# RCSfullschematic3.net
KiCad netlist of a schematic drawn in EAGLE
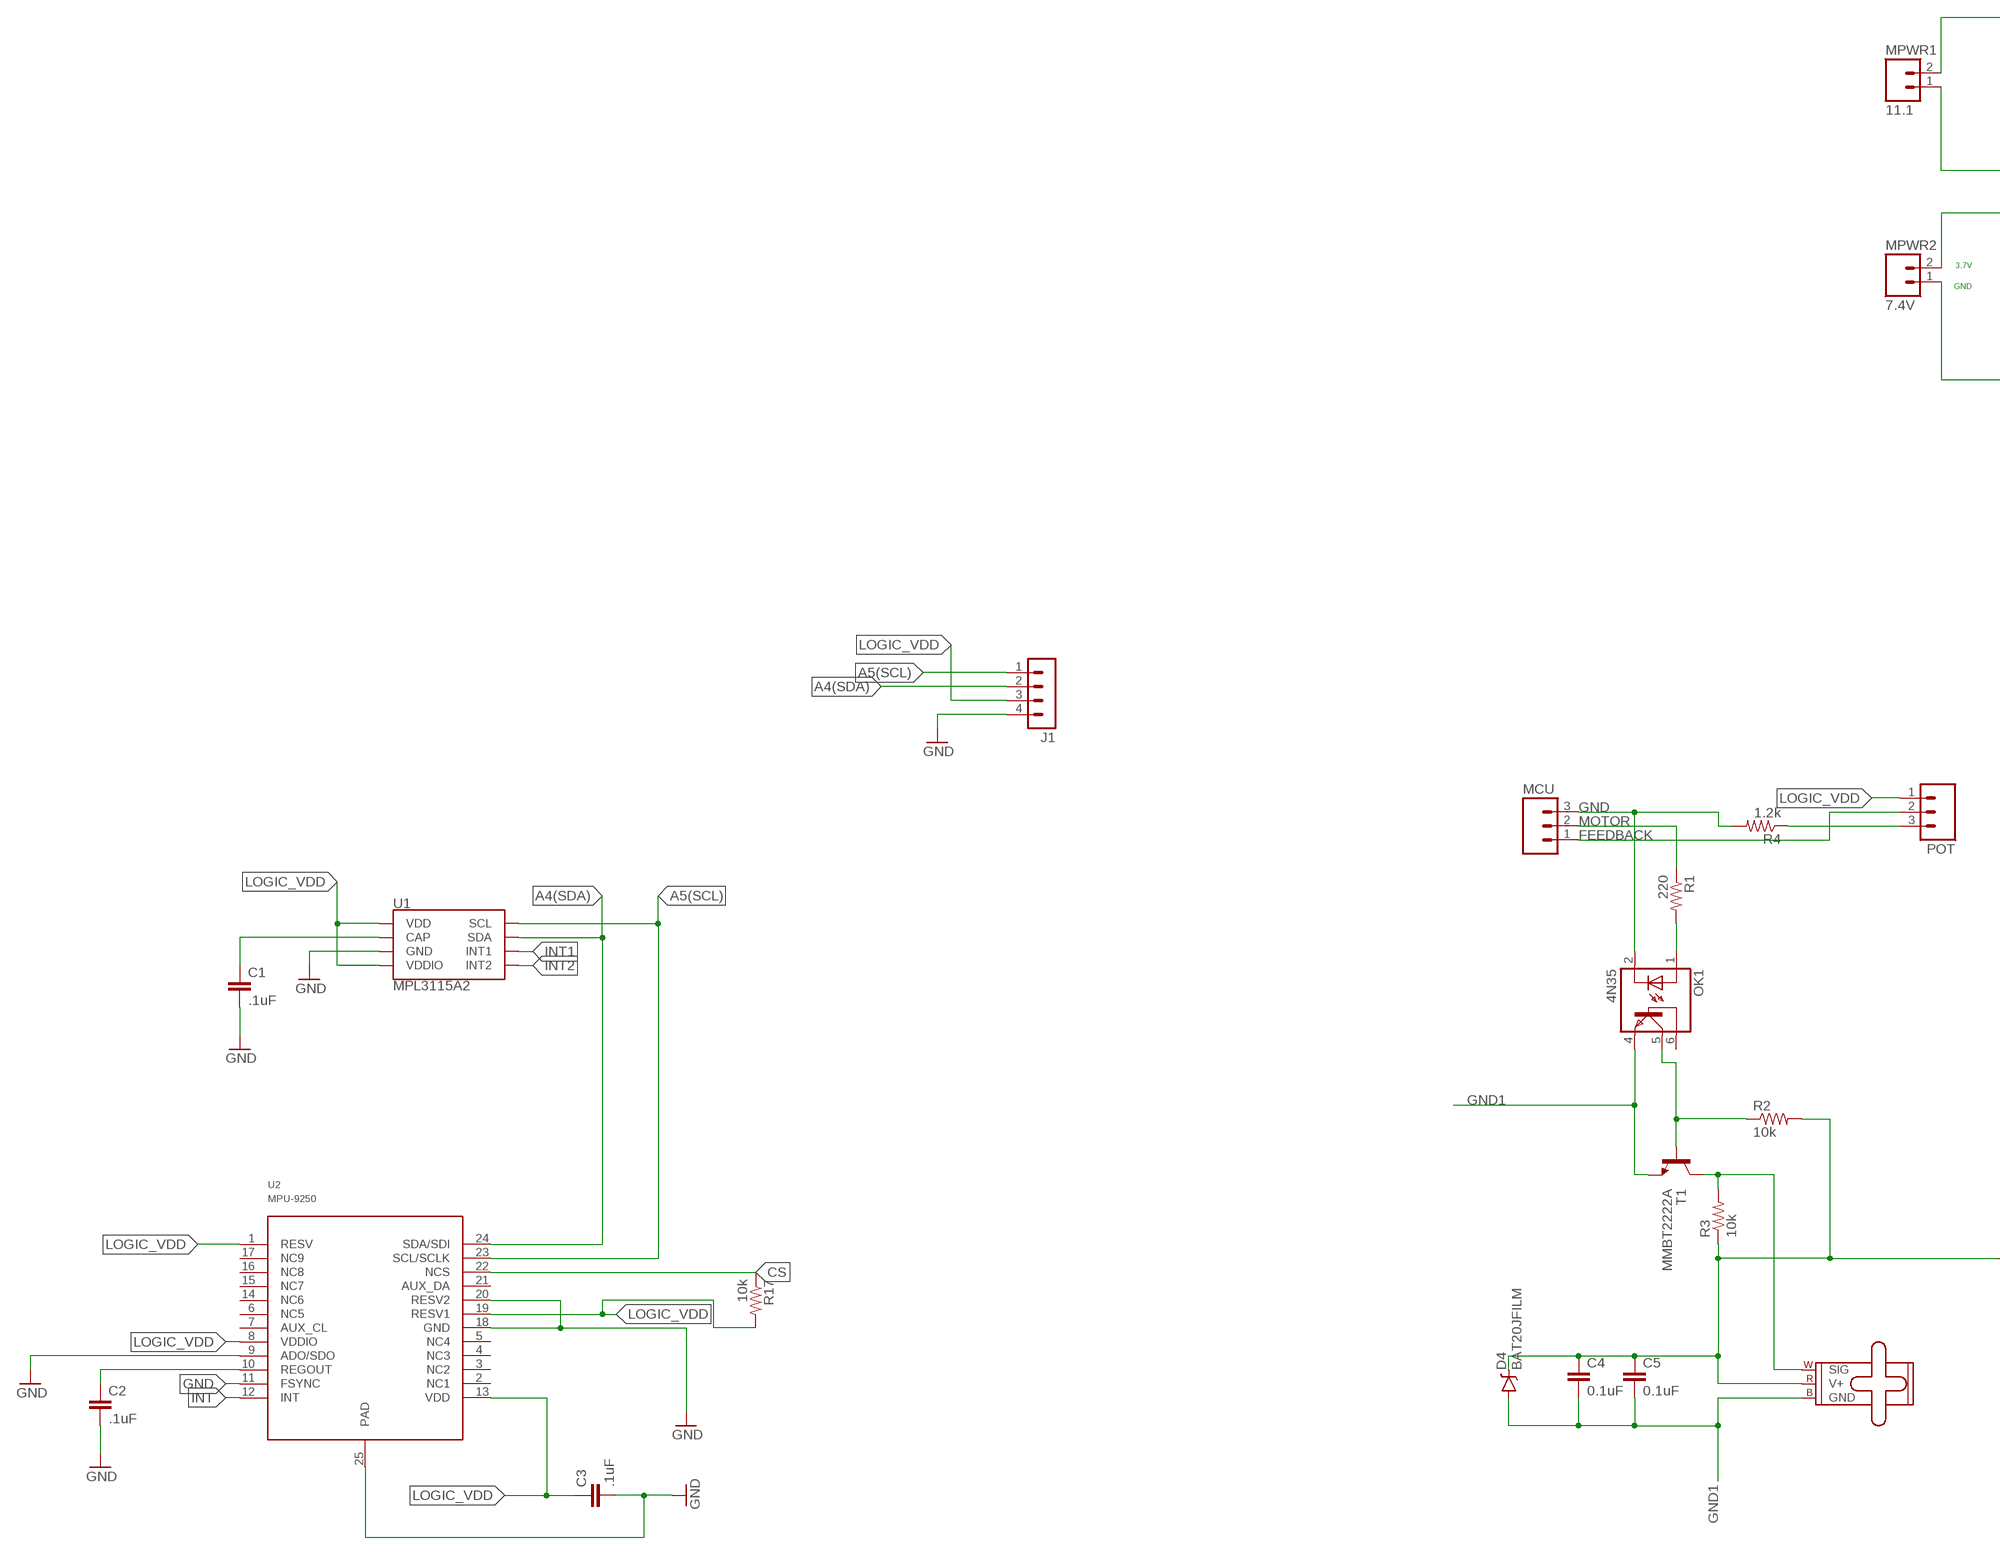
[diagram p0: schematic, sheet 1, part 1 of 2]
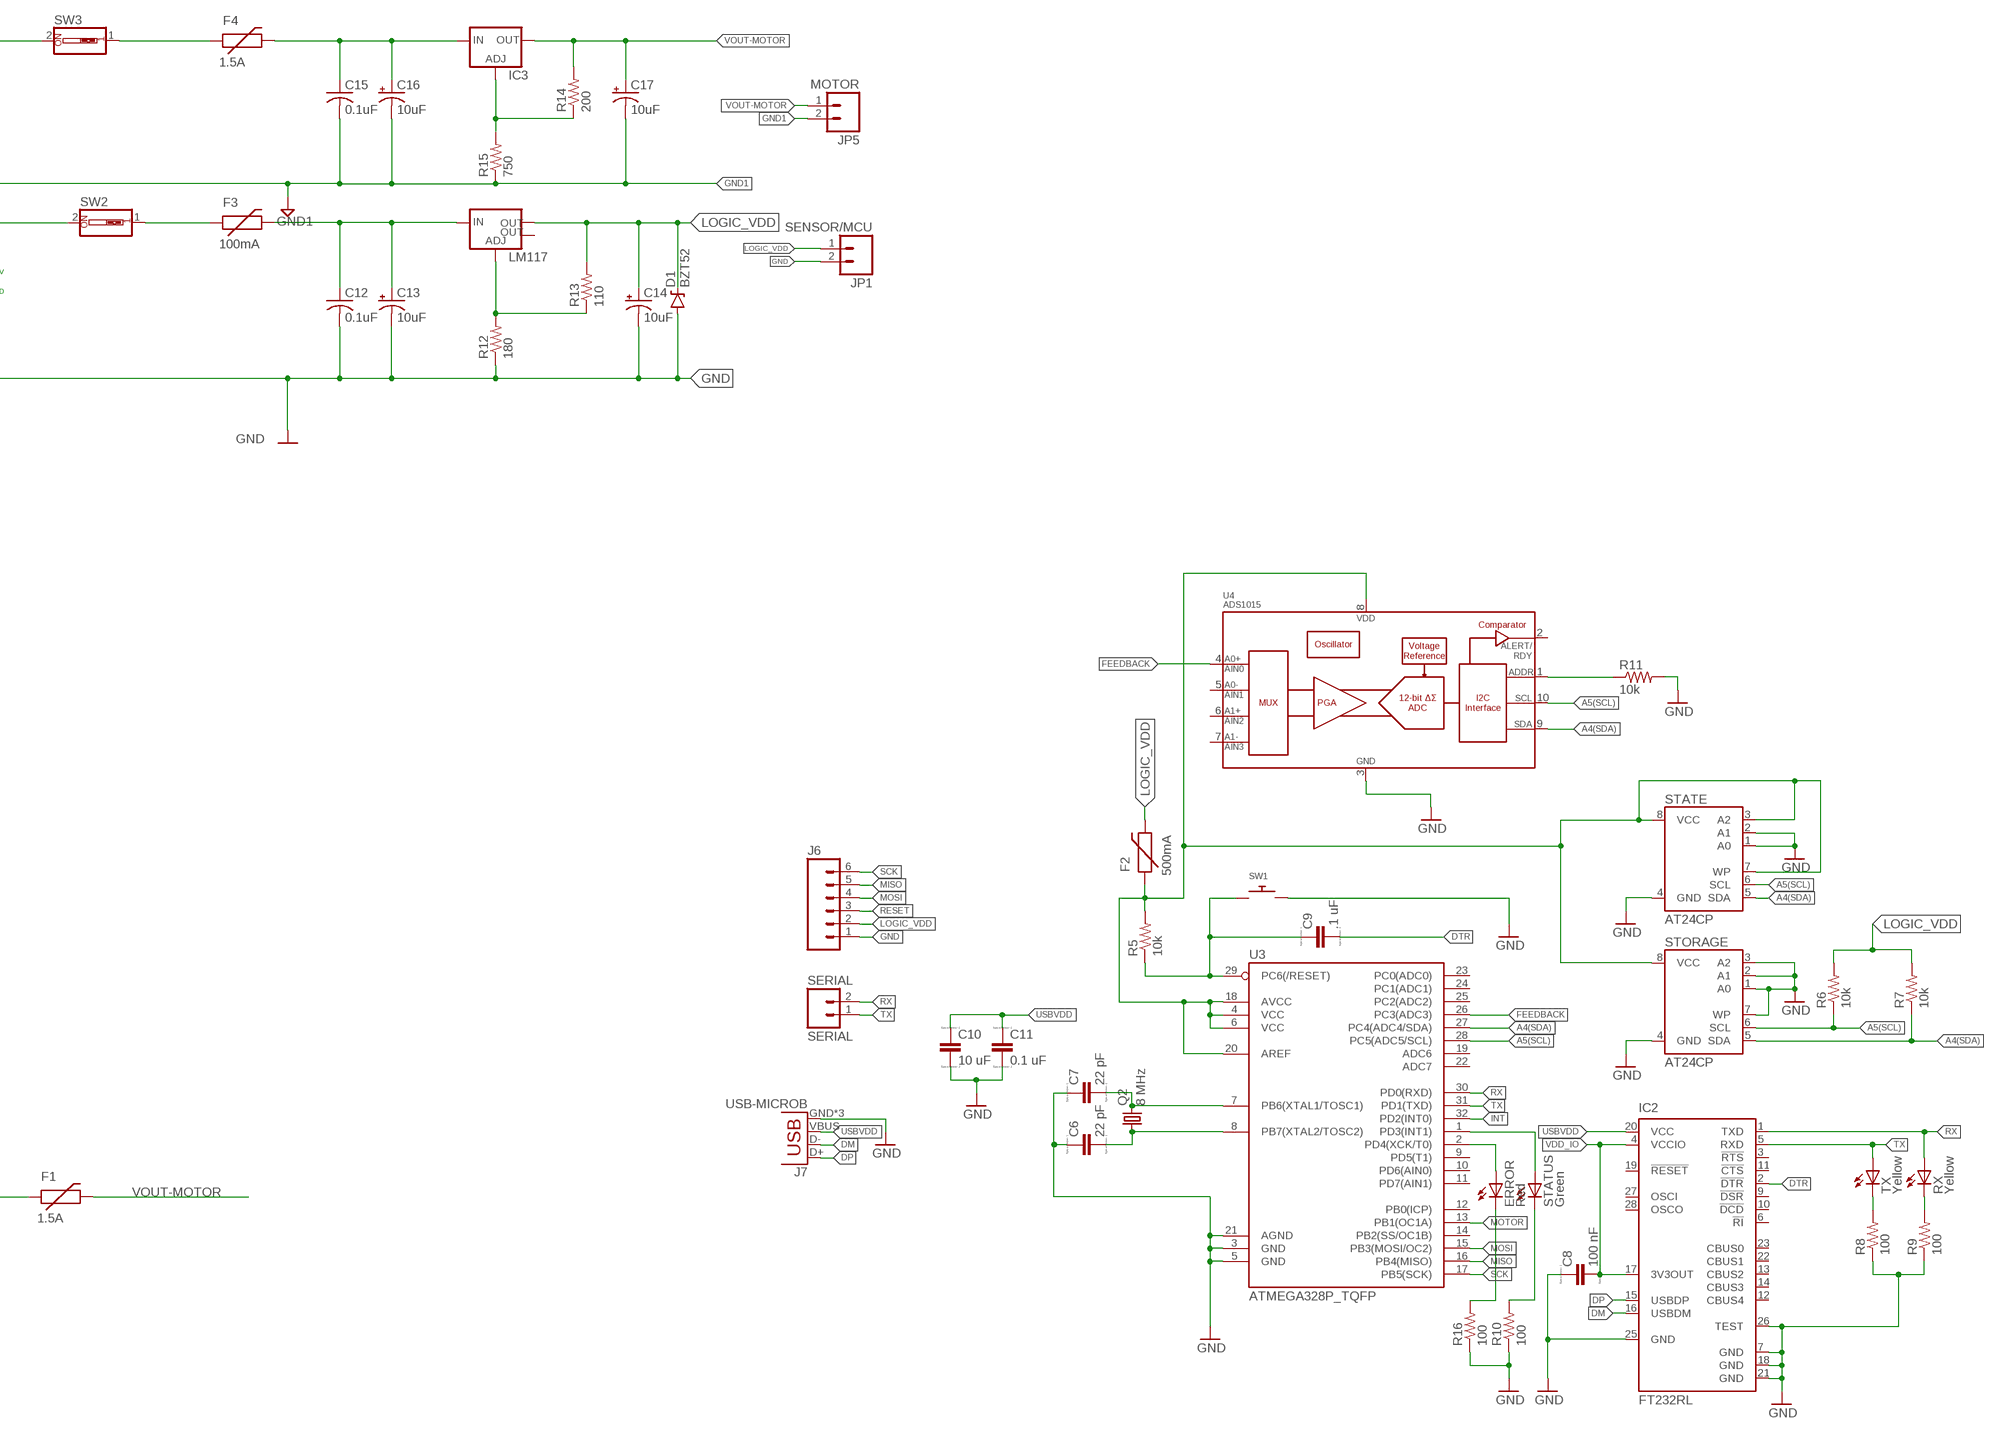
[diagram p1: schematic, sheet 1, part 2 of 2]

(export (version "E")
  (design (tool "Eeschema 10.0.6"))
  (components
    (comp (ref "C1")
      (value ".1uF")
      (footprint "eagle-import:1206")
      (libsource (lib "eagle-import") (part "10UF-1206-6.3V-20%"))
    )
    (comp (ref "C2")
      (value ".1uF")
      (footprint "eagle-import:1206")
      (libsource (lib "eagle-import") (part "10UF-1206-6.3V-20%"))
    )
    (comp (ref "C3")
      (value ".1uF")
      (footprint "eagle-import:1206")
      (libsource (lib "eagle-import") (part "10UF-1206-6.3V-20%"))
    )
    (comp (ref "C4")
      (value "0.1uF")
      (footprint "eagle-import:1206")
      (libsource (lib "eagle-import") (part "CAP1206"))
    )
    (comp (ref "C5")
      (value "0.1uF")
      (footprint "eagle-import:1206")
      (libsource (lib "eagle-import") (part "CAP1206"))
    )
    (comp (ref "C6")
      (value "22 pF")
      (footprint "eagle-import:C1206")
      (libsource (lib "eagle-import") (part "CC1206"))
    )
    (comp (ref "C7")
      (value "22 pF")
      (footprint "eagle-import:C1206")
      (libsource (lib "eagle-import") (part "CC1206"))
    )
    (comp (ref "C8")
      (value "100 nF")
      (footprint "eagle-import:C1206")
      (libsource (lib "eagle-import") (part "CC1206"))
    )
    (comp (ref "C9")
      (value ".1 uF")
      (footprint "eagle-import:C1206")
      (libsource (lib "eagle-import") (part "CC1206"))
    )
    (comp (ref "C10")
      (value "10 uF")
      (footprint "eagle-import:C1206")
      (libsource (lib "eagle-import") (part "CC1206"))
    )
    (comp (ref "C11")
      (value "0.1 uF")
      (footprint "eagle-import:C1206")
      (libsource (lib "eagle-import") (part "CC1206"))
    )
    (comp (ref "C12")
      (value "0.1uF")
      (footprint "eagle-import:C1206")
      (libsource (lib "eagle-import") (part "C-USC1206"))
    )
    (comp (ref "C13")
      (value "10uF")
      (footprint "eagle-import:EIA3216")
      (libsource (lib "eagle-import") (part "10UF-POLAR-EIA3216-16V-10%(TANT)"))
    )
    (comp (ref "C14")
      (value "10uF")
      (footprint "eagle-import:EIA3216")
      (libsource (lib "eagle-import") (part "10UF-POLAR-EIA3216-16V-10%(TANT)"))
    )
    (comp (ref "C15")
      (value "0.1uF")
      (footprint "eagle-import:C1206")
      (libsource (lib "eagle-import") (part "C-USC1206"))
    )
    (comp (ref "C16")
      (value "10uF")
      (footprint "eagle-import:EIA3216")
      (libsource (lib "eagle-import") (part "10UF-POLAR-EIA3216-16V-10%(TANT)"))
    )
    (comp (ref "C17")
      (value "10uF")
      (footprint "eagle-import:EIA3216")
      (libsource (lib "eagle-import") (part "10UF-POLAR-EIA3216-16V-10%(TANT)"))
    )
    (comp (ref "D1")
      (value "BZT52")
      (footprint "eagle-import:DIODE-BZT52")
      (libsource (lib "eagle-import") (part "DIODE-ZENER"))
    )
    (comp (ref "D4")
      (value "BAT20JFILM")
      (footprint "eagle-import:SOD-323")
      (libsource (lib "eagle-import") (part "BAT20JFILM"))
    )
    (comp (ref "ERROR")
      (value "Red")
      (footprint "eagle-import:CHIPLED_1206")
      (libsource (lib "eagle-import") (part "LEDCHIPLED_1206"))
    )
    (comp (ref "F1")
      (value "1.5A")
      (footprint "eagle-import:PTC-1206")
      (libsource (lib "eagle-import") (part "PTCSMD"))
    )
    (comp (ref "F2")
      (value "500mA")
      (footprint "eagle-import:PTC-1206")
      (libsource (lib "eagle-import") (part "PTCSMD"))
    )
    (comp (ref "F3")
      (value "100mA")
      (footprint "eagle-import:PTC-1206")
      (libsource (lib "eagle-import") (part "PTCSMD"))
    )
    (comp (ref "F4")
      (value "1.5A")
      (footprint "eagle-import:PTC-1206")
      (libsource (lib "eagle-import") (part "PTCSMD"))
    )
    (comp (ref "IC2")
      (value "FT232RL")
      (footprint "eagle-import:SSOP28")
      (libsource (lib "eagle-import") (part "FT232RL"))
    )
    (comp (ref "IC3")
      (value "LM317TS")
      (footprint "eagle-import:317TS")
      (libsource (lib "eagle-import") (part "LM317TS"))
    )
    (comp (ref "J1")
      (value "MA04-1")
      (footprint "eagle-import:MA04-1")
      (libsource (lib "eagle-import") (part "MA04-1"))
    )
    (comp (ref "J6")
      (value "M06LOCK")
      (footprint "eagle-import:1X06_LOCK")
      (libsource (lib "eagle-import") (part "M06LOCK"))
    )
    (comp (ref "J7")
      (value "USB-MICROB")
      (footprint "eagle-import:USB-MICROB")
      (libsource (lib "eagle-import") (part "USB-MICROB"))
    )
    (comp (ref "JP1")
      (value "SENSOR/MCU")
      (footprint "eagle-import:1X02")
      (libsource (lib "eagle-import") (part "M02PTH"))
    )
    (comp (ref "JP5")
      (value "MOTOR")
      (footprint "eagle-import:1X02")
      (libsource (lib "eagle-import") (part "M02PTH"))
    )
    (comp (ref "LM117")
      (value "V_REG_LM1117SOT223")
      (footprint "eagle-import:SOT223")
      (libsource (lib "eagle-import") (part "V_REG_LM1117SOT223"))
    )
    (comp (ref "MCU")
      (value "M03PTH")
      (footprint "eagle-import:1X03")
      (libsource (lib "eagle-import") (part "M03PTH"))
    )
    (comp (ref "MPWR1")
      (value "11.1")
      (footprint "eagle-import:1X02")
      (libsource (lib "eagle-import") (part "M02PTH"))
    )
    (comp (ref "MPWR2")
      (value "7.4V")
      (footprint "eagle-import:1X02")
      (libsource (lib "eagle-import") (part "M02PTH"))
    )
    (comp (ref "OK1")
      (value "4N35")
      (footprint "eagle-import:DIL06")
      (fields (field (name "MF") "FAIRCHILD SEMICONDUCTOR"))
      (libsource (lib "eagle-import") (part "4N35"))
    )
    (comp (ref "POT")
      (value "M03PTH")
      (footprint "eagle-import:1X03")
      (libsource (lib "eagle-import") (part "M03PTH"))
    )
    (comp (ref "Q2")
      (value "8 MHz")
      (footprint "eagle-import:HC49_S")
      (libsource (lib "eagle-import") (part "CRYSTALHC49S"))
    )
    (comp (ref "R1")
      (value "220")
      (footprint "eagle-import:1206")
      (libsource (lib "eagle-import") (part "RESISTOR1206"))
    )
    (comp (ref "R2")
      (value "10k")
      (footprint "eagle-import:1206")
      (libsource (lib "eagle-import") (part "RESISTOR1206"))
    )
    (comp (ref "R3")
      (value "10k")
      (footprint "eagle-import:1206")
      (libsource (lib "eagle-import") (part "RESISTOR1206"))
    )
    (comp (ref "R4")
      (value "1.2k")
      (footprint "eagle-import:1206")
      (libsource (lib "eagle-import") (part "RESISTOR1206"))
    )
    (comp (ref "R5")
      (value "10k")
      (footprint "eagle-import:R1206")
      (libsource (lib "eagle-import") (part "R-US_R1206"))
    )
    (comp (ref "R6")
      (value "10k")
      (footprint "eagle-import:R1206")
      (libsource (lib "eagle-import") (part "R-US_R1206"))
    )
    (comp (ref "R7")
      (value "10k")
      (footprint "eagle-import:R1206")
      (libsource (lib "eagle-import") (part "R-US_R1206"))
    )
    (comp (ref "R8")
      (value "100")
      (footprint "eagle-import:R1206")
      (libsource (lib "eagle-import") (part "R-US_R1206"))
    )
    (comp (ref "R9")
      (value "100")
      (footprint "eagle-import:R1206")
      (libsource (lib "eagle-import") (part "R-US_R1206"))
    )
    (comp (ref "R10")
      (value "100")
      (footprint "eagle-import:R1206")
      (libsource (lib "eagle-import") (part "R-US_R1206"))
    )
    (comp (ref "R11")
      (value "10k")
      (footprint "eagle-import:R1206")
      (libsource (lib "eagle-import") (part "R-US_R1206"))
    )
    (comp (ref "R12")
      (value "180")
      (footprint "eagle-import:M1206")
      (libsource (lib "eagle-import") (part "rcl_R-US_M1206"))
    )
    (comp (ref "R13")
      (value "110")
      (footprint "eagle-import:M1206")
      (libsource (lib "eagle-import") (part "rcl_R-US_M1206"))
    )
    (comp (ref "R14")
      (value "200")
      (footprint "eagle-import:M1206")
      (libsource (lib "eagle-import") (part "rcl_R-US_M1206"))
    )
    (comp (ref "R15")
      (value "750")
      (footprint "eagle-import:M1206")
      (libsource (lib "eagle-import") (part "rcl_R-US_M1206"))
    )
    (comp (ref "R16")
      (value "100")
      (footprint "eagle-import:R1206")
      (libsource (lib "eagle-import") (part "R-US_R1206"))
    )
    (comp (ref "R17")
      (value "10k")
      (footprint "eagle-import:1206")
      (libsource (lib "eagle-import") (part "RESISTOR1206"))
    )
    (comp (ref "RX")
      (value "Yellow")
      (footprint "eagle-import:CHIPLED_1206")
      (libsource (lib "eagle-import") (part "LEDCHIPLED_1206"))
    )
    (comp (ref "SERIAL")
      (value "SERIAL")
      (footprint "eagle-import:1X02")
      (libsource (lib "eagle-import") (part "M02PTH"))
    )
    (comp (ref "SERVO")
      (value "SMALL_SERVO")
      (footprint "eagle-import:1X03")
      (libsource (lib "eagle-import") (part "SMALL_SERVO"))
    )
    (comp (ref "STATE")
      (value "AT24CP")
      (footprint "eagle-import:DIL08")
      (fields (field (name "MPN") "AT24C1024BW-SH-B"))
      (libsource (lib "eagle-import") (part "AT24CP"))
    )
    (comp (ref "STATUS")
      (value "Green")
      (footprint "eagle-import:CHIPLED_1206")
      (libsource (lib "eagle-import") (part "LEDCHIPLED_1206"))
    )
    (comp (ref "STORAGE")
      (value "AT24CP")
      (footprint "eagle-import:DIL08")
      (fields (field (name "MPN") "AT24C1024BW-SH-B"))
      (libsource (lib "eagle-import") (part "AT24CP"))
    )
    (comp (ref "SW1")
      (value "SWITCH_PUSHBUTTONSOFTTOUCHSMD_SJ")
      (footprint "eagle-import:PUSHBUTTON_SMD_SJ")
      (libsource (lib "eagle-import") (part "SWITCH_PUSHBUTTONSOFTTOUCHSMD_SJ"))
    )
    (comp (ref "SW2")
      (value "SW_DIP-1")
      (footprint "eagle-import:EDG-01")
      (libsource (lib "eagle-import") (part "SW_DIP-1"))
    )
    (comp (ref "SW3")
      (value "SW_DIP-1")
      (footprint "eagle-import:EDG-01")
      (libsource (lib "eagle-import") (part "SW_DIP-1"))
    )
    (comp (ref "T1")
      (value "MMBT2222A")
      (footprint "eagle-import:SOT23-3")
      (libsource (lib "eagle-import") (part "TRANSISTOR_NPNMMBT2222A"))
    )
    (comp (ref "TX")
      (value "Yellow")
      (footprint "eagle-import:CHIPLED_1206")
      (libsource (lib "eagle-import") (part "LEDCHIPLED_1206"))
    )
    (comp (ref "U1")
      (value "MPL3115A2")
      (footprint "eagle-import:LGA-8")
      (libsource (lib "eagle-import") (part "MPL3115A2"))
    )
    (comp (ref "U2")
      (value "MPU-9250")
      (footprint "eagle-import:LEAD-QFN24")
      (libsource (lib "eagle-import") (part "MPU-9250"))
    )
    (comp (ref "U3")
      (value "ATMEGA328P_TQFP")
      (footprint "eagle-import:TQFP32-08")
      (libsource (lib "eagle-import") (part "ATMEGA328P_TQFP"))
    )
    (comp (ref "U4")
      (value "ADS1015")
      (footprint "eagle-import:MSOP10")
      (libsource (lib "eagle-import") (part "ADS1015"))
    )
  )
  (nets
    (net (code "1") (name "A4(SDA)") (class "Default")
      (node (ref "J1") (pin "2") (pinfunction "2_2") (pintype "passive"))
      (node (ref "R7") (pin "1") (pinfunction "1_1") (pintype "passive"))
      (node (ref "STATE") (pin "5") (pinfunction "SDA_5") (pintype "bidirectional"))
      (node (ref "STORAGE") (pin "5") (pinfunction "SDA_5") (pintype "bidirectional"))
      (node (ref "U1") (pin "7") (pinfunction "SDA_7") (pintype "bidirectional"))
      (node (ref "U2") (pin "24") (pinfunction "SDA/SDI_24") (pintype "bidirectional"))
      (node (ref "U3") (pin "27") (pinfunction "PC4(ADC4/SDA)_27") (pintype "bidirectional"))
      (node (ref "U4") (pin "9") (pinfunction "SDA_9") (pintype "bidirectional"))
    )
    (net (code "2") (name "A5(SCL)") (class "Default")
      (node (ref "J1") (pin "1") (pinfunction "1_1") (pintype "passive"))
      (node (ref "R6") (pin "1") (pinfunction "1_1") (pintype "passive"))
      (node (ref "STATE") (pin "6") (pinfunction "SCL_6") (pintype "bidirectional"))
      (node (ref "STORAGE") (pin "6") (pinfunction "SCL_6") (pintype "bidirectional"))
      (node (ref "U1") (pin "8") (pinfunction "SCL_8") (pintype "bidirectional"))
      (node (ref "U2") (pin "23") (pinfunction "SCL/SCLK_23") (pintype "bidirectional"))
      (node (ref "U3") (pin "28") (pinfunction "PC5(ADC5/SCL)_28") (pintype "bidirectional"))
      (node (ref "U4") (pin "10") (pinfunction "SCL_10") (pintype "bidirectional"))
    )
    (net (code "3") (name "CS") (class "Default")
      (node (ref "R17") (pin "1") (pinfunction "1_1") (pintype "passive"))
      (node (ref "U2") (pin "22") (pinfunction "NCS_22") (pintype "bidirectional"))
    )
    (net (code "4") (name "DM") (class "Default")
      (node (ref "IC2") (pin "16") (pinfunction "USBDM_16") (pintype "bidirectional"))
      (node (ref "J7") (pin "D-") (pinfunction "D-_D-") (pintype "bidirectional"))
    )
    (net (code "5") (name "DP") (class "Default")
      (node (ref "IC2") (pin "15") (pinfunction "USBDP_15") (pintype "bidirectional"))
      (node (ref "J7") (pin "D+") (pinfunction "D+_D+") (pintype "bidirectional"))
    )
    (net (code "6") (name "DTR") (class "Default")
      (node (ref "C9") (pin "2") (pinfunction "2_2") (pintype "passive"))
      (node (ref "IC2") (pin "2") (pinfunction "~{DTR}_2") (pintype "output"))
    )
    (net (code "7") (name "FEEDBACK") (class "Default")
      (node (ref "MCU") (pin "1") (pinfunction "1_1") (pintype "passive"))
      (node (ref "POT") (pin "2") (pinfunction "2_2") (pintype "passive"))
      (node (ref "U3") (pin "26") (pinfunction "PC3(ADC3)_26") (pintype "bidirectional"))
      (node (ref "U4") (pin "4") (pinfunction "AIN0_4") (pintype "bidirectional"))
    )
    (net (code "8") (name "GND") (class "Default")
      (node (ref "C1") (pin "2") (pinfunction "2_2") (pintype "passive"))
      (node (ref "C10") (pin "2") (pinfunction "2_2") (pintype "passive"))
      (node (ref "C11") (pin "2") (pinfunction "2_2") (pintype "passive"))
      (node (ref "C12") (pin "2") (pinfunction "2_2") (pintype "passive"))
      (node (ref "C13") (pin "-") (pinfunction "-_-") (pintype "passive"))
      (node (ref "C14") (pin "-") (pinfunction "-_-") (pintype "passive"))
      (node (ref "C2") (pin "2") (pinfunction "2_2") (pintype "passive"))
      (node (ref "C3") (pin "2") (pinfunction "2_2") (pintype "passive"))
      (node (ref "C6") (pin "1") (pinfunction "1_1") (pintype "passive"))
      (node (ref "C7") (pin "1") (pinfunction "1_1") (pintype "passive"))
      (node (ref "C8") (pin "1") (pinfunction "1_1") (pintype "passive"))
      (node (ref "D1") (pin "A") (pinfunction "A_A") (pintype "passive"))
      (node (ref "IC2") (pin "18") (pinfunction "GND_18") (pintype "power_in"))
      (node (ref "IC2") (pin "21") (pinfunction "GND_21") (pintype "power_in"))
      (node (ref "IC2") (pin "25") (pinfunction "GND_25") (pintype "power_in"))
      (node (ref "IC2") (pin "26") (pinfunction "TEST_26") (pintype "input"))
      (node (ref "IC2") (pin "7") (pinfunction "GND_7") (pintype "power_in"))
      (node (ref "J1") (pin "4") (pinfunction "4_4") (pintype "passive"))
      (node (ref "J6") (pin "1") (pinfunction "1_1") (pintype "passive"))
      (node (ref "J7") (pin "GND") (pinfunction "GND_GND") (pintype "bidirectional"))
      (node (ref "J7") (pin "MT1") (pinfunction "GND_MT1") (pintype "bidirectional"))
      (node (ref "J7") (pin "MT2") (pinfunction "GND_MT2") (pintype "bidirectional"))
      (node (ref "JP1") (pin "2") (pinfunction "2_2") (pintype "passive"))
      (node (ref "MCU") (pin "3") (pinfunction "3_3") (pintype "passive"))
      (node (ref "MPWR2") (pin "1") (pinfunction "1_1") (pintype "passive"))
      (node (ref "OK1") (pin "2") (pinfunction "C_2") (pintype "passive"))
      (node (ref "R10") (pin "1") (pinfunction "1_1") (pintype "passive"))
      (node (ref "R11") (pin "2") (pinfunction "2_2") (pintype "passive"))
      (node (ref "R12") (pin "1") (pinfunction "1_1") (pintype "passive"))
      (node (ref "R16") (pin "1") (pinfunction "1_1") (pintype "passive"))
      (node (ref "R4") (pin "2") (pinfunction "2_2") (pintype "passive"))
      (node (ref "R8") (pin "1") (pinfunction "1_1") (pintype "passive"))
      (node (ref "R9") (pin "1") (pinfunction "1_1") (pintype "passive"))
      (node (ref "STATE") (pin "1") (pinfunction "A0_1") (pintype "input"))
      (node (ref "STATE") (pin "2") (pinfunction "A1_2") (pintype "input"))
      (node (ref "STATE") (pin "4") (pinfunction "GND_4") (pintype "power_in"))
      (node (ref "STORAGE") (pin "1") (pinfunction "A0_1") (pintype "input"))
      (node (ref "STORAGE") (pin "2") (pinfunction "A1_2") (pintype "input"))
      (node (ref "STORAGE") (pin "3") (pinfunction "A2_3") (pintype "input"))
      (node (ref "STORAGE") (pin "4") (pinfunction "GND_4") (pintype "power_in"))
      (node (ref "STORAGE") (pin "7") (pinfunction "WP_7") (pintype "input"))
      (node (ref "SW1") (pin "P$2") (pinfunction "P$2_P$2") (pintype "passive"))
      (node (ref "U1") (pin "3") (pinfunction "GND_3") (pintype "power_in"))
      (node (ref "U2") (pin "11") (pinfunction "FSYNC_11") (pintype "bidirectional"))
      (node (ref "U2") (pin "18") (pinfunction "GND_18") (pintype "bidirectional"))
      (node (ref "U2") (pin "20") (pinfunction "RESV2_20") (pintype "bidirectional"))
      (node (ref "U2") (pin "25") (pinfunction "PAD_25") (pintype "bidirectional"))
      (node (ref "U2") (pin "9") (pinfunction "ADO/SDO_9") (pintype "bidirectional"))
      (node (ref "U3") (pin "21") (pinfunction "AGND_21") (pintype "bidirectional"))
      (node (ref "U3") (pin "3") (pinfunction "GND_3") (pintype "bidirectional"))
      (node (ref "U3") (pin "5") (pinfunction "GND_5") (pintype "bidirectional"))
      (node (ref "U4") (pin "3") (pinfunction "VSS_3") (pintype "bidirectional"))
    )
    (net (code "9") (name "GND1") (class "Default")
      (node (ref "C15") (pin "2") (pinfunction "2_2") (pintype "passive"))
      (node (ref "C16") (pin "-") (pinfunction "-_-") (pintype "passive"))
      (node (ref "C17") (pin "-") (pinfunction "-_-") (pintype "passive"))
      (node (ref "C4") (pin "2") (pinfunction "2_2") (pintype "passive"))
      (node (ref "C5") (pin "2") (pinfunction "2_2") (pintype "passive"))
      (node (ref "D4") (pin "A") (pinfunction "A_A") (pintype "passive"))
      (node (ref "JP5") (pin "2") (pinfunction "2_2") (pintype "passive"))
      (node (ref "MPWR1") (pin "1") (pinfunction "1_1") (pintype "passive"))
      (node (ref "OK1") (pin "4") (pinfunction "EMI_4") (pintype "passive"))
      (node (ref "R15") (pin "1") (pinfunction "1_1") (pintype "passive"))
      (node (ref "SERVO") (pin "3") (pinfunction "GND_3") (pintype "bidirectional"))
      (node (ref "T1") (pin "2") (pinfunction "E_2") (pintype "passive"))
    )
    (net (code "10") (name "INT") (class "Default")
      (node (ref "U2") (pin "12") (pinfunction "INT_12") (pintype "bidirectional"))
      (node (ref "U3") (pin "32") (pinfunction "PD2(INT0)_32") (pintype "bidirectional"))
    )
    (net (code "11") (name "INT1") (class "Default")
      (node (ref "U1") (pin "6") (pinfunction "INT1_6") (pintype "output"))
    )
    (net (code "12") (name "INT2") (class "Default")
      (node (ref "U1") (pin "5") (pinfunction "INT2_5") (pintype "output"))
    )
    (net (code "13") (name "LOGIC_VDD") (class "Default")
      (node (ref "C14") (pin "+") (pinfunction "+_+") (pintype "passive"))
      (node (ref "C3") (pin "1") (pinfunction "1_1") (pintype "passive"))
      (node (ref "D1") (pin "C") (pinfunction "C_C") (pintype "passive"))
      (node (ref "F2") (pin "2") (pinfunction "2_2") (pintype "bidirectional"))
      (node (ref "J1") (pin "3") (pinfunction "3_3") (pintype "passive"))
      (node (ref "J6") (pin "2") (pinfunction "2_2") (pintype "passive"))
      (node (ref "JP1") (pin "1") (pinfunction "1_1") (pintype "passive"))
      (node (ref "LM117") (pin "2") (pinfunction "OUT_2") (pintype "output"))
      (node (ref "POT") (pin "1") (pinfunction "1_1") (pintype "passive"))
      (node (ref "R13") (pin "2") (pinfunction "2_2") (pintype "passive"))
      (node (ref "R17") (pin "2") (pinfunction "2_2") (pintype "passive"))
      (node (ref "R6") (pin "2") (pinfunction "2_2") (pintype "passive"))
      (node (ref "R7") (pin "2") (pinfunction "2_2") (pintype "passive"))
      (node (ref "U1") (pin "1") (pinfunction "VDD_1") (pintype "power_in"))
      (node (ref "U1") (pin "4") (pinfunction "VDDIO_4") (pintype "power_in"))
      (node (ref "U2") (pin "1") (pinfunction "RESV_1") (pintype "bidirectional"))
      (node (ref "U2") (pin "13") (pinfunction "VDD_13") (pintype "bidirectional"))
      (node (ref "U2") (pin "19") (pinfunction "RESV1_19") (pintype "bidirectional"))
      (node (ref "U2") (pin "8") (pinfunction "VDDIO_8") (pintype "bidirectional"))
    )
    (net (code "14") (name "MISO") (class "Default")
      (node (ref "J6") (pin "5") (pinfunction "5_5") (pintype "passive"))
      (node (ref "U3") (pin "16") (pinfunction "PB4(MISO)_16") (pintype "bidirectional"))
    )
    (net (code "15") (name "MOSI") (class "Default")
      (node (ref "J6") (pin "4") (pinfunction "4_4") (pintype "passive"))
      (node (ref "U3") (pin "15") (pinfunction "PB3(MOSI/OC2)_15") (pintype "bidirectional"))
    )
    (net (code "16") (name "MOTOR") (class "Default")
      (node (ref "MCU") (pin "2") (pinfunction "2_2") (pintype "passive"))
      (node (ref "R1") (pin "1") (pinfunction "1_1") (pintype "passive"))
      (node (ref "U3") (pin "13") (pinfunction "PB1(OC1A)_13") (pintype "bidirectional"))
    )
    (net (code "17") (name "Net-(ERROR-PadC)") (class "Default")
      (node (ref "ERROR") (pin "C") (pinfunction "C_C") (pintype "passive"))
      (node (ref "R16") (pin "2") (pinfunction "2_2") (pintype "passive"))
    )
    (net (code "18") (name "Net-(F3-Pad1)") (class "Default")
      (node (ref "F3") (pin "1") (pinfunction "1_1") (pintype "bidirectional"))
      (node (ref "SW2") (pin "1") (pinfunction "1_1") (pintype "passive"))
    )
    (net (code "19") (name "Net-(F4-Pad1)") (class "Default")
      (node (ref "F4") (pin "1") (pinfunction "1_1") (pintype "bidirectional"))
      (node (ref "SW3") (pin "1") (pinfunction "1_1") (pintype "passive"))
    )
    (net (code "20") (name "Net-(IC3-ADJ)") (class "Default")
      (node (ref "IC3") (pin "1") (pinfunction "ADJ_1") (pintype "input"))
      (node (ref "R14") (pin "1") (pinfunction "1_1") (pintype "passive"))
      (node (ref "R15") (pin "2") (pinfunction "2_2") (pintype "passive"))
    )
    (net (code "21") (name "Net-(IC3-IN)") (class "Default")
      (node (ref "C15") (pin "1") (pinfunction "1_1") (pintype "passive"))
      (node (ref "C16") (pin "+") (pinfunction "+_+") (pintype "passive"))
      (node (ref "F4") (pin "2") (pinfunction "2_2") (pintype "bidirectional"))
      (node (ref "IC3") (pin "3") (pinfunction "IN_3") (pintype "input"))
    )
    (net (code "22") (name "Net-(LM117-ADJ)") (class "Default")
      (node (ref "LM117") (pin "1") (pinfunction "ADJ_1") (pintype "input"))
      (node (ref "R12") (pin "2") (pinfunction "2_2") (pintype "passive"))
      (node (ref "R13") (pin "1") (pinfunction "1_1") (pintype "passive"))
    )
    (net (code "23") (name "Net-(LM117-IN)") (class "Default")
      (node (ref "C12") (pin "1") (pinfunction "1_1") (pintype "passive"))
      (node (ref "C13") (pin "+") (pinfunction "+_+") (pintype "passive"))
      (node (ref "F3") (pin "2") (pinfunction "2_2") (pintype "bidirectional"))
      (node (ref "LM117") (pin "3") (pinfunction "IN_3") (pintype "input"))
    )
    (net (code "24") (name "Net-(MPWR1-Pad2)") (class "Default")
      (node (ref "MPWR1") (pin "2") (pinfunction "2_2") (pintype "passive"))
      (node (ref "SW3") (pin "2") (pinfunction "2_2") (pintype "passive"))
    )
    (net (code "25") (name "Net-(MPWR2-Pad2)") (class "Default")
      (node (ref "MPWR2") (pin "2") (pinfunction "2_2") (pintype "passive"))
      (node (ref "SW2") (pin "2") (pinfunction "2_2") (pintype "passive"))
    )
    (net (code "26") (name "Net-(OK1-A)") (class "Default")
      (node (ref "OK1") (pin "1") (pinfunction "A_1") (pintype "passive"))
      (node (ref "R1") (pin "2") (pinfunction "2_2") (pintype "passive"))
    )
    (net (code "27") (name "Net-(OK1-COL)") (class "Default")
      (node (ref "OK1") (pin "5") (pinfunction "COL_5") (pintype "passive"))
      (node (ref "R2") (pin "1") (pinfunction "1_1") (pintype "passive"))
      (node (ref "T1") (pin "1") (pinfunction "B_1") (pintype "passive"))
    )
    (net (code "28") (name "Net-(POT-Pad3)") (class "Default")
      (node (ref "POT") (pin "3") (pinfunction "3_3") (pintype "passive"))
      (node (ref "R4") (pin "1") (pinfunction "1_1") (pintype "passive"))
    )
    (net (code "29") (name "Net-(R8-Pad2)") (class "Default")
      (node (ref "R8") (pin "2") (pinfunction "2_2") (pintype "passive"))
      (node (ref "TX") (pin "C") (pinfunction "C_C") (pintype "passive"))
    )
    (net (code "30") (name "Net-(R9-Pad2)") (class "Default")
      (node (ref "R9") (pin "2") (pinfunction "2_2") (pintype "passive"))
      (node (ref "RX") (pin "C") (pinfunction "C_C") (pintype "passive"))
    )
    (net (code "31") (name "Net-(R10-Pad2)") (class "Default")
      (node (ref "R10") (pin "2") (pinfunction "2_2") (pintype "passive"))
      (node (ref "STATUS") (pin "C") (pinfunction "C_C") (pintype "passive"))
    )
    (net (code "32") (name "Net-(SERVO-SIG)") (class "Default")
      (node (ref "R3") (pin "2") (pinfunction "2_2") (pintype "passive"))
      (node (ref "SERVO") (pin "1") (pinfunction "SIG_1") (pintype "bidirectional"))
      (node (ref "T1") (pin "3") (pinfunction "C_3") (pintype "passive"))
    )
    (net (code "33") (name "Net-(SERVO-V+)") (class "Default")
      (node (ref "C4") (pin "1") (pinfunction "1_1") (pintype "passive"))
      (node (ref "C5") (pin "1") (pinfunction "1_1") (pintype "passive"))
      (node (ref "D4") (pin "C") (pinfunction "C_C") (pintype "passive"))
      (node (ref "F1") (pin "1") (pinfunction "1_1") (pintype "bidirectional"))
      (node (ref "R2") (pin "2") (pinfunction "2_2") (pintype "passive"))
      (node (ref "R3") (pin "1") (pinfunction "1_1") (pintype "passive"))
      (node (ref "SERVO") (pin "2") (pinfunction "V+_2") (pintype "bidirectional"))
    )
    (net (code "34") (name "Net-(STATE-A2)") (class "Default")
      (node (ref "F2") (pin "1") (pinfunction "1_1") (pintype "bidirectional"))
      (node (ref "R5") (pin "2") (pinfunction "2_2") (pintype "passive"))
      (node (ref "STATE") (pin "3") (pinfunction "A2_3") (pintype "input"))
      (node (ref "STATE") (pin "7") (pinfunction "WP_7") (pintype "input"))
      (node (ref "STATE") (pin "8") (pinfunction "VCC_8") (pintype "power_in"))
      (node (ref "STORAGE") (pin "8") (pinfunction "VCC_8") (pintype "power_in"))
      (node (ref "U3") (pin "18") (pinfunction "AVCC_18") (pintype "bidirectional"))
      (node (ref "U3") (pin "20") (pinfunction "AREF_20") (pintype "bidirectional"))
      (node (ref "U3") (pin "4") (pinfunction "VCC_4") (pintype "bidirectional"))
      (node (ref "U3") (pin "6") (pinfunction "VCC_6") (pintype "bidirectional"))
      (node (ref "U4") (pin "8") (pinfunction "VDD_8") (pintype "bidirectional"))
    )
    (net (code "35") (name "Net-(U1-CAP)") (class "Default")
      (node (ref "C1") (pin "1") (pinfunction "1_1") (pintype "passive"))
      (node (ref "U1") (pin "2") (pinfunction "CAP_2") (pintype "power_in"))
    )
    (net (code "36") (name "Net-(U2-REGOUT)") (class "Default")
      (node (ref "C2") (pin "1") (pinfunction "1_1") (pintype "passive"))
      (node (ref "U2") (pin "10") (pinfunction "REGOUT_10") (pintype "bidirectional"))
    )
    (net (code "37") (name "Net-(U3-PB6(XTAL1{slash}TOSC1))") (class "Default")
      (node (ref "C7") (pin "2") (pinfunction "2_2") (pintype "passive"))
      (node (ref "Q2") (pin "2") (pinfunction "2_2") (pintype "passive"))
      (node (ref "U3") (pin "7") (pinfunction "PB6(XTAL1/TOSC1)_7") (pintype "bidirectional"))
    )
    (net (code "38") (name "Net-(U3-PB7(XTAL2{slash}TOSC2))") (class "Default")
      (node (ref "C6") (pin "2") (pinfunction "2_2") (pintype "passive"))
      (node (ref "Q2") (pin "1") (pinfunction "1_1") (pintype "passive"))
      (node (ref "U3") (pin "8") (pinfunction "PB7(XTAL2/TOSC2)_8") (pintype "bidirectional"))
    )
    (net (code "39") (name "Net-(U3-PD3(INT1))") (class "Default")
      (node (ref "STATUS") (pin "A") (pinfunction "A_A") (pintype "passive"))
      (node (ref "U3") (pin "1") (pinfunction "PD3(INT1)_1") (pintype "bidirectional"))
    )
    (net (code "40") (name "Net-(U3-PD4(XCK{slash}T0))") (class "Default")
      (node (ref "ERROR") (pin "A") (pinfunction "A_A") (pintype "passive"))
      (node (ref "U3") (pin "2") (pinfunction "PD4(XCK/T0)_2") (pintype "bidirectional"))
    )
    (net (code "41") (name "Net-(U4-ADDR)") (class "Default")
      (node (ref "R11") (pin "1") (pinfunction "1_1") (pintype "passive"))
      (node (ref "U4") (pin "1") (pinfunction "ADDR_1") (pintype "bidirectional"))
    )
    (net (code "42") (name "RESET") (class "Default")
      (node (ref "C9") (pin "1") (pinfunction "1_1") (pintype "passive"))
      (node (ref "J6") (pin "3") (pinfunction "3_3") (pintype "passive"))
      (node (ref "R5") (pin "1") (pinfunction "1_1") (pintype "passive"))
      (node (ref "SW1") (pin "P$1") (pinfunction "P$1_P$1") (pintype "passive"))
      (node (ref "U3") (pin "29") (pinfunction "PC6(/RESET)_29") (pintype "bidirectional"))
    )
    (net (code "43") (name "RX") (class "Default")
      (node (ref "IC2") (pin "1") (pinfunction "TXD_1") (pintype "output"))
      (node (ref "RX") (pin "A") (pinfunction "A_A") (pintype "passive"))
      (node (ref "SERIAL") (pin "2") (pinfunction "2_2") (pintype "passive"))
      (node (ref "U3") (pin "30") (pinfunction "PD0(RXD)_30") (pintype "bidirectional"))
    )
    (net (code "44") (name "SCK") (class "Default")
      (node (ref "J6") (pin "6") (pinfunction "6_6") (pintype "passive"))
      (node (ref "U3") (pin "17") (pinfunction "PB5(SCK)_17") (pintype "bidirectional"))
    )
    (net (code "45") (name "TX") (class "Default")
      (node (ref "IC2") (pin "5") (pinfunction "RXD_5") (pintype "input"))
      (node (ref "SERIAL") (pin "1") (pinfunction "1_1") (pintype "passive"))
      (node (ref "TX") (pin "A") (pinfunction "A_A") (pintype "passive"))
      (node (ref "U3") (pin "31") (pinfunction "PD1(TXD)_31") (pintype "bidirectional"))
    )
    (net (code "46") (name "USBVDD") (class "Default")
      (node (ref "C10") (pin "1") (pinfunction "1_1") (pintype "passive"))
      (node (ref "C11") (pin "1") (pinfunction "1_1") (pintype "passive"))
      (node (ref "IC2") (pin "20") (pinfunction "VCC_20") (pintype "power_in"))
      (node (ref "J7") (pin "VBUS") (pinfunction "VBUS_VBUS") (pintype "bidirectional"))
    )
    (net (code "47") (name "VDD_IO") (class "Default")
      (node (ref "C8") (pin "2") (pinfunction "2_2") (pintype "passive"))
      (node (ref "IC2") (pin "17") (pinfunction "3V3OUT_17") (pintype "output"))
      (node (ref "IC2") (pin "4") (pinfunction "VCCIO_4") (pintype "power_in"))
    )
    (net (code "48") (name "VOUT-MOTOR") (class "Default")
      (node (ref "C17") (pin "+") (pinfunction "+_+") (pintype "passive"))
      (node (ref "F1") (pin "2") (pinfunction "2_2") (pintype "bidirectional"))
      (node (ref "IC3") (pin "2") (pinfunction "OUT_2") (pintype "passive"))
      (node (ref "JP5") (pin "1") (pinfunction "1_1") (pintype "passive"))
      (node (ref "R14") (pin "2") (pinfunction "2_2") (pintype "passive"))
    )
    (net (code "49") (name "unconnected-(IC2-CBUS0-Pad23)") (class "Default")
      (node (ref "IC2") (pin "23") (pinfunction "CBUS0_23") (pintype "bidirectional"))
    )
    (net (code "50") (name "unconnected-(IC2-CBUS1-Pad22)") (class "Default")
      (node (ref "IC2") (pin "22") (pinfunction "CBUS1_22") (pintype "bidirectional"))
    )
    (net (code "51") (name "unconnected-(IC2-CBUS2-Pad13)") (class "Default")
      (node (ref "IC2") (pin "13") (pinfunction "CBUS2_13") (pintype "bidirectional"))
    )
    (net (code "52") (name "unconnected-(IC2-CBUS3-Pad14)") (class "Default")
      (node (ref "IC2") (pin "14") (pinfunction "CBUS3_14") (pintype "bidirectional"))
    )
    (net (code "53") (name "unconnected-(IC2-CBUS4-Pad12)") (class "Default")
      (node (ref "IC2") (pin "12") (pinfunction "CBUS4_12") (pintype "bidirectional"))
    )
    (net (code "54") (name "unconnected-(IC2-OSCI-Pad27)") (class "Default")
      (node (ref "IC2") (pin "27") (pinfunction "OSCI_27") (pintype "input"))
    )
    (net (code "55") (name "unconnected-(IC2-OSCO-Pad28)") (class "Default")
      (node (ref "IC2") (pin "28") (pinfunction "OSCO_28") (pintype "output"))
    )
    (net (code "56") (name "unconnected-(IC2-~{CTS}-Pad11)") (class "Default")
      (node (ref "IC2") (pin "11") (pinfunction "~{CTS}_11") (pintype "input"))
    )
    (net (code "57") (name "unconnected-(IC2-~{DCD}-Pad10)") (class "Default")
      (node (ref "IC2") (pin "10") (pinfunction "~{DCD}_10") (pintype "input"))
    )
    (net (code "58") (name "unconnected-(IC2-~{DSR}-Pad9)") (class "Default")
      (node (ref "IC2") (pin "9") (pinfunction "~{DSR}_9") (pintype "input"))
    )
    (net (code "59") (name "unconnected-(IC2-~{RESET}-Pad19)") (class "Default")
      (node (ref "IC2") (pin "19") (pinfunction "~{RESET}_19") (pintype "input"))
    )
    (net (code "60") (name "unconnected-(IC2-~{RI}-Pad6)") (class "Default")
      (node (ref "IC2") (pin "6") (pinfunction "~{RI}_6") (pintype "input"))
    )
    (net (code "61") (name "unconnected-(IC2-~{RTS}-Pad3)") (class "Default")
      (node (ref "IC2") (pin "3") (pinfunction "~{RTS}_3") (pintype "output"))
    )
    (net (code "62") (name "unconnected-(LM117-OUT-Pad4)") (class "Default")
      (node (ref "LM117") (pin "4") (pinfunction "OUT_4") (pintype "output"))
    )
    (net (code "63") (name "unconnected-(OK1-BAS-Pad6)") (class "Default")
      (node (ref "OK1") (pin "6") (pinfunction "BAS_6") (pintype "passive"))
    )
    (net (code "64") (name "unconnected-(U2-AUX_CL-Pad7)") (class "Default")
      (node (ref "U2") (pin "7") (pinfunction "AUX_CL_7") (pintype "bidirectional"))
    )
    (net (code "65") (name "unconnected-(U2-AUX_DA-Pad21)") (class "Default")
      (node (ref "U2") (pin "21") (pinfunction "AUX_DA_21") (pintype "bidirectional"))
    )
    (net (code "66") (name "unconnected-(U2-NC1-Pad2)") (class "Default")
      (node (ref "U2") (pin "2") (pinfunction "NC1_2") (pintype "bidirectional"))
    )
    (net (code "67") (name "unconnected-(U2-NC2-Pad3)") (class "Default")
      (node (ref "U2") (pin "3") (pinfunction "NC2_3") (pintype "bidirectional"))
    )
    (net (code "68") (name "unconnected-(U2-NC3-Pad4)") (class "Default")
      (node (ref "U2") (pin "4") (pinfunction "NC3_4") (pintype "bidirectional"))
    )
    (net (code "69") (name "unconnected-(U2-NC4-Pad5)") (class "Default")
      (node (ref "U2") (pin "5") (pinfunction "NC4_5") (pintype "bidirectional"))
    )
    (net (code "70") (name "unconnected-(U2-NC5-Pad6)") (class "Default")
      (node (ref "U2") (pin "6") (pinfunction "NC5_6") (pintype "bidirectional"))
    )
    (net (code "71") (name "unconnected-(U2-NC6-Pad14)") (class "Default")
      (node (ref "U2") (pin "14") (pinfunction "NC6_14") (pintype "bidirectional"))
    )
    (net (code "72") (name "unconnected-(U2-NC7-Pad15)") (class "Default")
      (node (ref "U2") (pin "15") (pinfunction "NC7_15") (pintype "bidirectional"))
    )
    (net (code "73") (name "unconnected-(U2-NC8-Pad16)") (class "Default")
      (node (ref "U2") (pin "16") (pinfunction "NC8_16") (pintype "bidirectional"))
    )
    (net (code "74") (name "unconnected-(U2-NC9-Pad17)") (class "Default")
      (node (ref "U2") (pin "17") (pinfunction "NC9_17") (pintype "bidirectional"))
    )
    (net (code "75") (name "unconnected-(U3-ADC6-Pad19)") (class "Default")
      (node (ref "U3") (pin "19") (pinfunction "ADC6_19") (pintype "bidirectional"))
    )
    (net (code "76") (name "unconnected-(U3-ADC7-Pad22)") (class "Default")
      (node (ref "U3") (pin "22") (pinfunction "ADC7_22") (pintype "bidirectional"))
    )
    (net (code "77") (name "unconnected-(U3-PB0(ICP)-Pad12)") (class "Default")
      (node (ref "U3") (pin "12") (pinfunction "PB0(ICP)_12") (pintype "bidirectional"))
    )
    (net (code "78") (name "unconnected-(U3-PB2(SS{slash}OC1B)-Pad14)") (class "Default")
      (node (ref "U3") (pin "14") (pinfunction "PB2(SS/OC1B)_14") (pintype "bidirectional"))
    )
    (net (code "79") (name "unconnected-(U3-PC0(ADC0)-Pad23)") (class "Default")
      (node (ref "U3") (pin "23") (pinfunction "PC0(ADC0)_23") (pintype "bidirectional"))
    )
    (net (code "80") (name "unconnected-(U3-PC1(ADC1)-Pad24)") (class "Default")
      (node (ref "U3") (pin "24") (pinfunction "PC1(ADC1)_24") (pintype "bidirectional"))
    )
    (net (code "81") (name "unconnected-(U3-PC2(ADC2)-Pad25)") (class "Default")
      (node (ref "U3") (pin "25") (pinfunction "PC2(ADC2)_25") (pintype "bidirectional"))
    )
    (net (code "82") (name "unconnected-(U3-PD5(T1)-Pad9)") (class "Default")
      (node (ref "U3") (pin "9") (pinfunction "PD5(T1)_9") (pintype "bidirectional"))
    )
    (net (code "83") (name "unconnected-(U3-PD6(AIN0)-Pad10)") (class "Default")
      (node (ref "U3") (pin "10") (pinfunction "PD6(AIN0)_10") (pintype "bidirectional"))
    )
    (net (code "84") (name "unconnected-(U3-PD7(AIN1)-Pad11)") (class "Default")
      (node (ref "U3") (pin "11") (pinfunction "PD7(AIN1)_11") (pintype "bidirectional"))
    )
    (net (code "85") (name "unconnected-(U4-AIN1-Pad5)") (class "Default")
      (node (ref "U4") (pin "5") (pinfunction "AIN1_5") (pintype "bidirectional"))
    )
    (net (code "86") (name "unconnected-(U4-AIN2-Pad6)") (class "Default")
      (node (ref "U4") (pin "6") (pinfunction "AIN2_6") (pintype "bidirectional"))
    )
    (net (code "87") (name "unconnected-(U4-AIN3-Pad7)") (class "Default")
      (node (ref "U4") (pin "7") (pinfunction "AIN3_7") (pintype "bidirectional"))
    )
    (net (code "88") (name "unconnected-(U4-ALERT{slash}RDY-Pad2)") (class "Default")
      (node (ref "U4") (pin "2") (pinfunction "ALERT/RDY_2") (pintype "bidirectional"))
    )
  )
)
